# Fri3D_2020_GameOn_02.net
KiCad netlist of a schematic drawn in Altium Designer
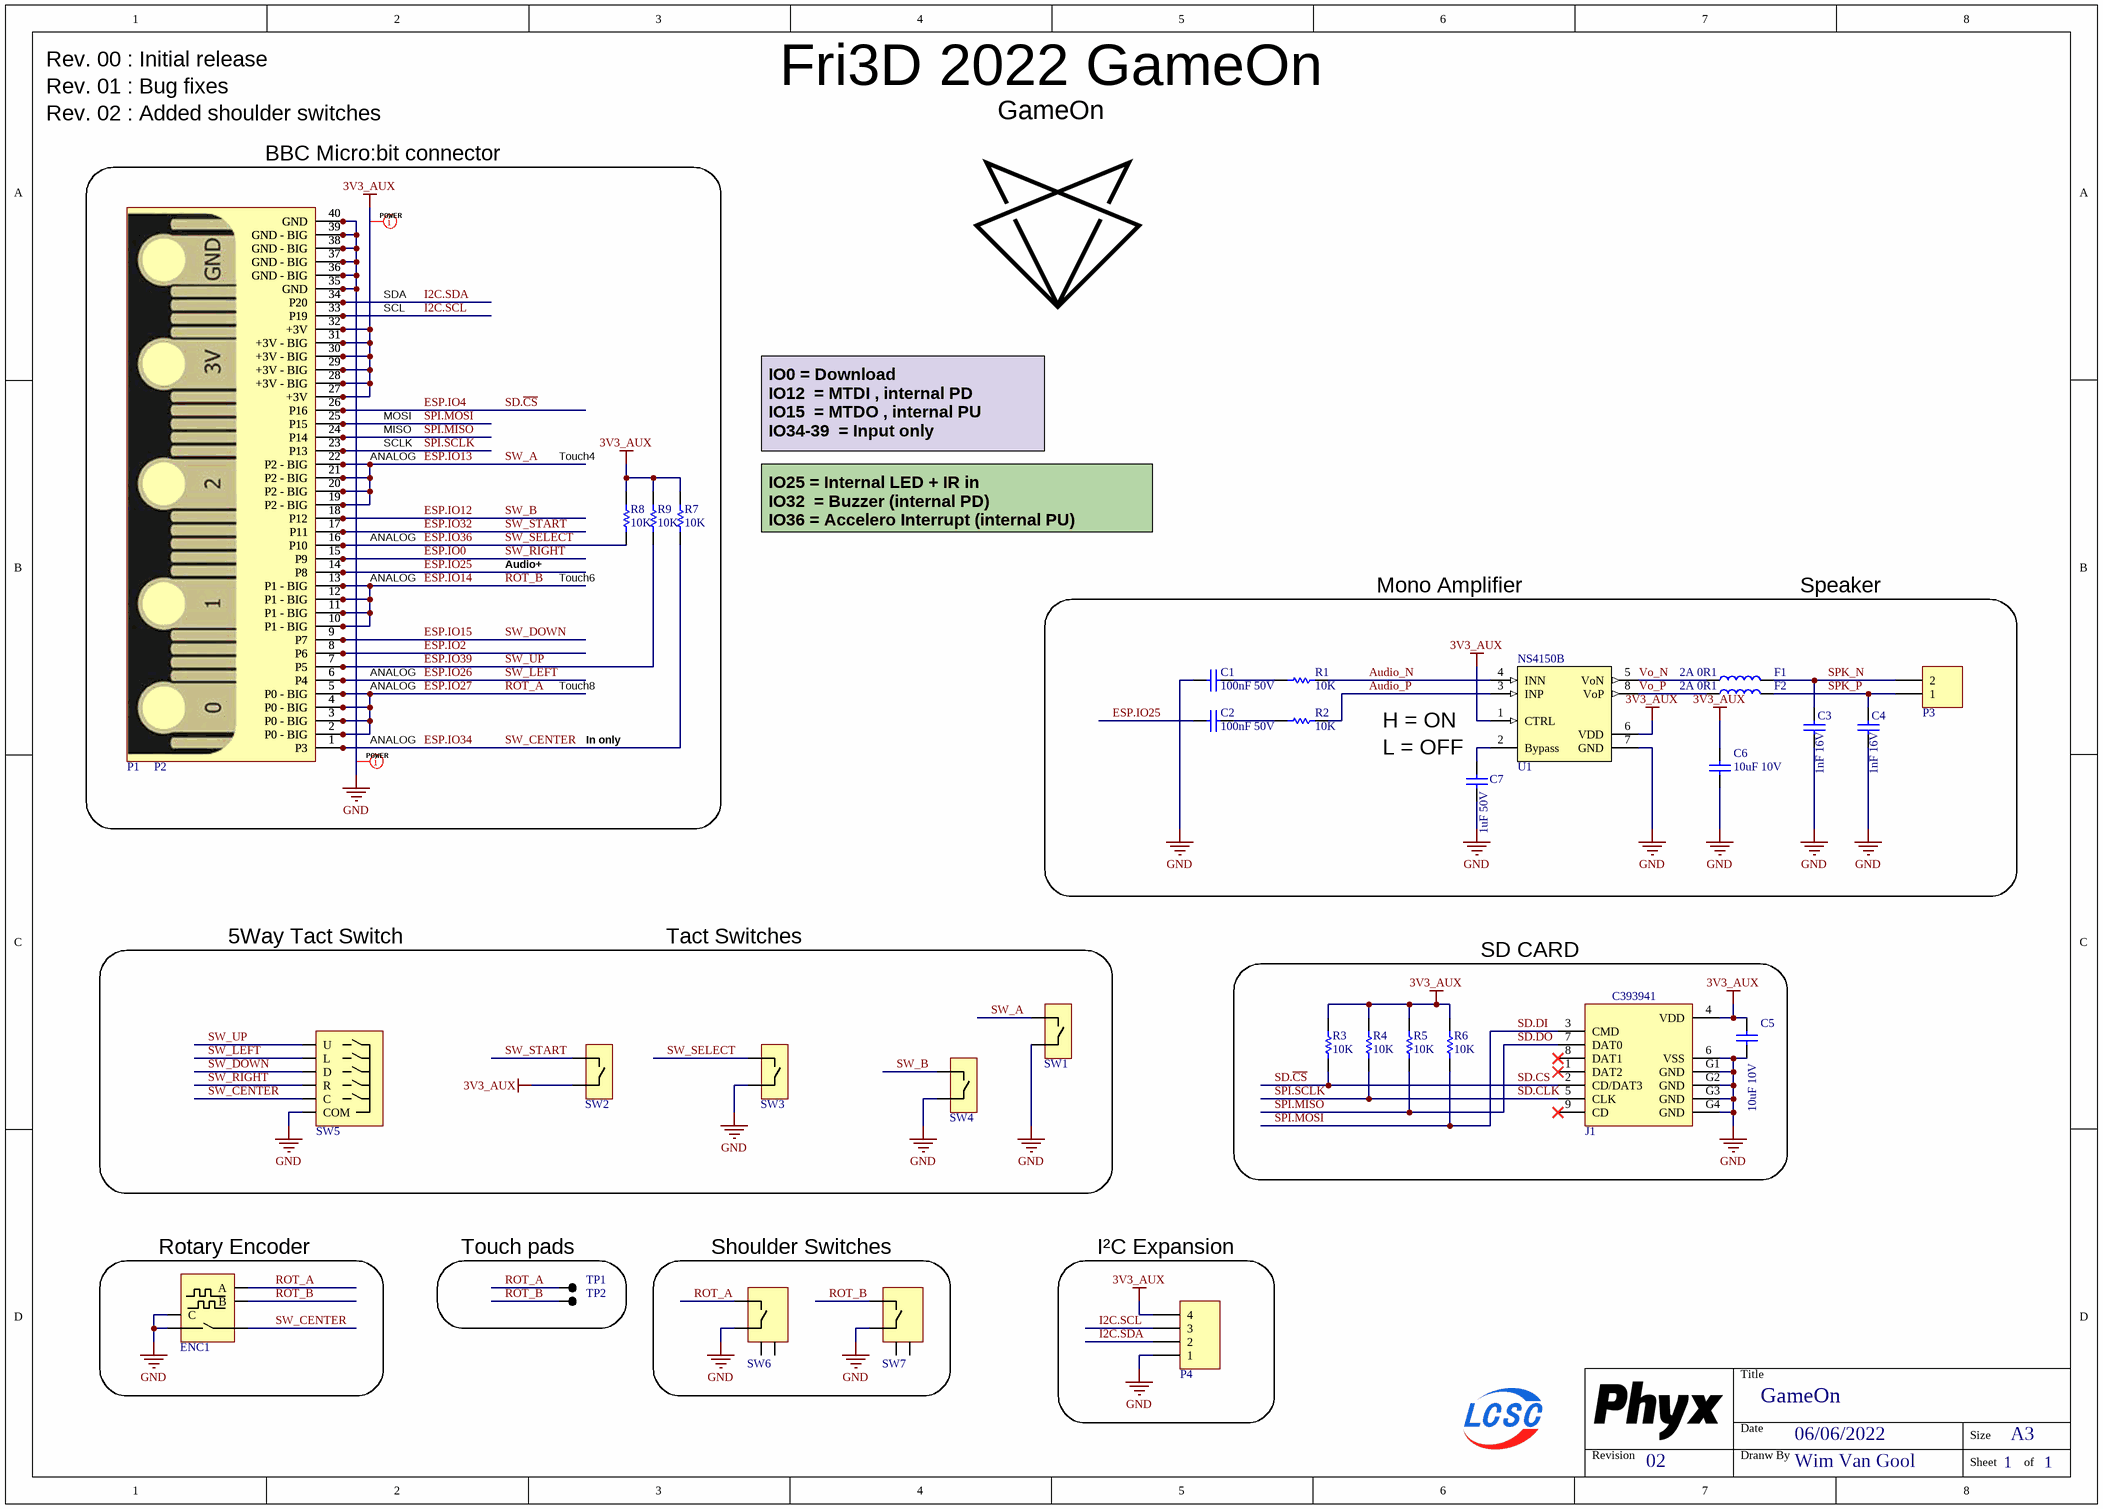
[diagram p0: Fri3D_2020_GameOn_02.SchDoc]

(export (version "E")
  (design (tool "Eeschema 10.0.6"))
  (components
    (comp (ref "C1")
      (value "100nF 50V")
      (footprint "C0603_N")
      (description "Capacitor Ceramic")
      (fields (field (name "Comment") "CAP_CERAMIC"))
      (libsource (lib "Phyx_Components") (part "CAP_CERAMIC"))
    )
    (comp (ref "C2")
      (value "100nF 50V")
      (footprint "C0603_N")
      (description "Capacitor Ceramic")
      (fields (field (name "Comment") "CAP_CERAMIC"))
      (libsource (lib "Phyx_Components") (part "CAP_CERAMIC"))
    )
    (comp (ref "C3")
      (value "1nF 16V")
      (footprint "C0603_N")
      (description "Capacitor Ceramic")
      (fields (field (name "Comment") "CAP_CERAMIC"))
      (libsource (lib "Phyx_Components") (part "CAP_CERAMIC"))
    )
    (comp (ref "C4")
      (value "1nF 16V")
      (footprint "C0603_N")
      (description "Capacitor Ceramic")
      (fields (field (name "Comment") "CAP_CERAMIC"))
      (libsource (lib "Phyx_Components") (part "CAP_CERAMIC"))
    )
    (comp (ref "C5")
      (value "10uF 10V")
      (footprint "C0805_N")
      (description "Capacitor Ceramic")
      (fields (field (name "Comment") "CAP_CERAMIC"))
      (libsource (lib "Phyx_Components") (part "CAP_CERAMIC"))
    )
    (comp (ref "C6")
      (value "10uF 10V")
      (footprint "C0805_N")
      (description "Capacitor Ceramic")
      (fields (field (name "Comment") "CAP_CERAMIC"))
      (libsource (lib "Phyx_Components") (part "CAP_CERAMIC"))
    )
    (comp (ref "C7")
      (value "1uF 50V")
      (footprint "C0603_N")
      (description "Capacitor Ceramic")
      (fields (field (name "Comment") "CAP_CERAMIC"))
      (libsource (lib "Phyx_Components") (part "CAP_CERAMIC"))
    )
    (comp (ref "ENC1")
      (value "Rotary Encoder with Switch")
      (footprint "PEC11-4215F-S0024")
      (libsource (lib "Phyx_Components") (part "ROT_ENC_3P_SW"))
    )
    (comp (ref "F1")
      (value "2A 0R1")
      (footprint "L0805")
      (fields (field (name "Comment") "FERRITE"))
      (libsource (lib "Phyx_Components") (part "FERRITE"))
    )
    (comp (ref "F2")
      (value "2A 0R1")
      (footprint "L0805")
      (fields (field (name "Comment") "FERRITE"))
      (libsource (lib "Phyx_Components") (part "FERRITE"))
    )
    (comp (ref "J1")
      (value "Micro SD PiPo Push-Push")
      (footprint "TFP09-2-12B")
      (description "=Description")
      (fields (field (name "SUPPLIER PART NUMBER 1") "C393941"))
      (libsource (lib "Phyx_Components") (part "TFP09-2-12B"))
    )
    (comp (ref "P1")
      (value "MicroBit 90deg connector Cylconn")
      (footprint "MicroBIT_CYLCONN_SMD_90")
      (libsource (lib "Phyx_Components") (part "Header 40_MicroBit"))
    )
    (comp (ref "P2")
      (value "MicroBit 180deg connector Cylconn")
      (footprint "MicroBIT_CYLCONN_SMD_180")
      (libsource (lib "Phyx_Components") (part "Header 40_MicroBit"))
    )
    (comp (ref "P3")
      (value "Header 2")
      (footprint "HDR1X2")
      (libsource (lib "Phyx_Components") (part "Header 2"))
    )
    (comp (ref "P4")
      (value "Header 4")
      (footprint "HDR1X4")
      (libsource (lib "Phyx_Components") (part "Header 4"))
    )
    (comp (ref "R1")
      (value "10K")
      (footprint "R0603_N")
      (fields (field (name "Comment") "RESISTOR"))
      (libsource (lib "Phyx_Components") (part "RESISTOR"))
    )
    (comp (ref "R2")
      (value "10K")
      (footprint "R0603_N")
      (fields (field (name "Comment") "RESISTOR"))
      (libsource (lib "Phyx_Components") (part "RESISTOR"))
    )
    (comp (ref "R3")
      (value "10K")
      (footprint "R0603_N")
      (fields (field (name "Comment") "RESISTOR"))
      (libsource (lib "Phyx_Components") (part "RESISTOR"))
    )
    (comp (ref "R4")
      (value "10K")
      (footprint "R0603_N")
      (fields (field (name "Comment") "RESISTOR"))
      (libsource (lib "Phyx_Components") (part "RESISTOR"))
    )
    (comp (ref "R5")
      (value "10K")
      (footprint "R0603_N")
      (fields (field (name "Comment") "RESISTOR"))
      (libsource (lib "Phyx_Components") (part "RESISTOR"))
    )
    (comp (ref "R6")
      (value "10K")
      (footprint "R0603_N")
      (fields (field (name "Comment") "RESISTOR"))
      (libsource (lib "Phyx_Components") (part "RESISTOR"))
    )
    (comp (ref "R7")
      (value "10K")
      (footprint "R0603_N")
      (fields (field (name "Comment") "RESISTOR"))
      (libsource (lib "Phyx_Components") (part "RESISTOR"))
    )
    (comp (ref "R8")
      (value "10K")
      (footprint "R0603_N")
      (fields (field (name "Comment") "RESISTOR"))
      (libsource (lib "Phyx_Components") (part "RESISTOR"))
    )
    (comp (ref "R9")
      (value "10K")
      (footprint "R0603_N")
      (fields (field (name "Comment") "RESISTOR"))
      (libsource (lib "Phyx_Components") (part "RESISTOR"))
    )
    (comp (ref "SW1")
      (value "Default TH TACT")
      (footprint "TACTSW")
      (libsource (lib "Phyx_Components") (part "SW_TACT"))
    )
    (comp (ref "SW2")
      (value "Default TH TACT")
      (footprint "TACTSW")
      (libsource (lib "Phyx_Components") (part "SW_TACT"))
    )
    (comp (ref "SW3")
      (value "Default TH TACT")
      (footprint "TACTSW")
      (libsource (lib "Phyx_Components") (part "SW_TACT"))
    )
    (comp (ref "SW4")
      (value "Default TH TACT")
      (footprint "TACTSW")
      (libsource (lib "Phyx_Components") (part "SW_TACT"))
    )
    (comp (ref "SW5")
      (value "5Way Tact switch")
      (footprint "TACTSW_5W_K1-1506DN-01")
      (libsource (lib "Phyx_Components") (part "SW_TACT_5WAY"))
    )
    (comp (ref "SW6")
      (value "Tact switch, RA, 3,85mm")
      (footprint "TACTSW_RA_385")
      (libsource (lib "Phyx_Components") (part "SW_TACT_RA"))
    )
    (comp (ref "SW7")
      (value "Tact switch, RA, 3,85mm")
      (footprint "TACTSW_RA_385")
      (libsource (lib "Phyx_Components") (part "SW_TACT_RA"))
    )
    (comp (ref "TP1")
      (value "TEST_PAD")
      (footprint "TP_1.2mm")
      (libsource (lib "Phyx_Components") (part "TEST_PAD"))
    )
    (comp (ref "TP2")
      (value "TEST_PAD")
      (footprint "TP_1.2mm")
      (libsource (lib "Phyx_Components") (part "TEST_PAD"))
    )
    (comp (ref "U1")
      (value "NS4150B")
      (footprint "MAX_uSOP8")
      (description "=Description")
      (fields (field (name "Comment") "5W Class D mono amplifier inducter-less Differential input MSOP8"))
      (libsource (lib "Phyx_Components") (part "NS4150"))
    )
  )
  (nets
    (net (code "1") (name "/Audio_N") (class "Default")
      (node (ref "R1") (pin "2") (pinfunction "2_2") (pintype "passive"))
      (node (ref "U1") (pin "4") (pinfunction "INN_4") (pintype "input"))
    )
    (net (code "2") (name "/Audio_P") (class "Default")
      (node (ref "R2") (pin "2") (pinfunction "2_2") (pintype "passive"))
      (node (ref "U1") (pin "3") (pinfunction "INP_3") (pintype "input"))
    )
    (net (code "3") (name "/ESP.IO0") (class "Default")
      (node (ref "P1") (pin "15") (pinfunction "P9_15") (pintype "passive"))
      (node (ref "P2") (pin "15") (pinfunction "P9_15") (pintype "passive"))
      (node (ref "SW5") (pin "5") (pinfunction "R_5") (pintype "passive"))
    )
    (net (code "4") (name "/ESP.IO2") (class "Default")
      (node (ref "P1") (pin "8") (pinfunction "P6_8") (pintype "passive"))
      (node (ref "P2") (pin "8") (pinfunction "P6_8") (pintype "passive"))
    )
    (net (code "5") (name "/ESP.IO4") (class "Default")
      (node (ref "J1") (pin "2") (pinfunction "CD/DAT3_2") (pintype "passive"))
      (node (ref "P1") (pin "26") (pinfunction "P16_26") (pintype "passive"))
      (node (ref "P2") (pin "26") (pinfunction "P16_26") (pintype "passive"))
      (node (ref "R3") (pin "2") (pinfunction "2_2") (pintype "passive"))
    )
    (net (code "6") (name "/ESP.IO12") (class "Default")
      (node (ref "P1") (pin "18") (pinfunction "P12_18") (pintype "passive"))
      (node (ref "P2") (pin "18") (pinfunction "P12_18") (pintype "passive"))
      (node (ref "SW4") (pin "1") (pinfunction "1_1") (pintype "passive"))
    )
    (net (code "7") (name "/ESP.IO13") (class "Default")
      (node (ref "P1") (pin "19") (pinfunction "P2_-_BIG_19") (pintype "passive"))
      (node (ref "P1") (pin "20") (pinfunction "P2_-_BIG_20") (pintype "passive"))
      (node (ref "P1") (pin "21") (pinfunction "P2_-_BIG_21") (pintype "passive"))
      (node (ref "P1") (pin "22") (pinfunction "P2_-_BIG_22") (pintype "passive"))
      (node (ref "P2") (pin "19") (pinfunction "P2_-_BIG_19") (pintype "passive"))
      (node (ref "P2") (pin "20") (pinfunction "P2_-_BIG_20") (pintype "passive"))
      (node (ref "P2") (pin "21") (pinfunction "P2_-_BIG_21") (pintype "passive"))
      (node (ref "P2") (pin "22") (pinfunction "P2_-_BIG_22") (pintype "passive"))
      (node (ref "SW1") (pin "1") (pinfunction "1_1") (pintype "passive"))
    )
    (net (code "8") (name "/ESP.IO14") (class "Default")
      (node (ref "ENC1") (pin "B") (pinfunction "B_B") (pintype "passive"))
      (node (ref "P1") (pin "10") (pinfunction "P1_-_BIG_10") (pintype "passive"))
      (node (ref "P1") (pin "11") (pinfunction "P1_-_BIG_11") (pintype "passive"))
      (node (ref "P1") (pin "12") (pinfunction "P1_-_BIG_12") (pintype "passive"))
      (node (ref "P1") (pin "13") (pinfunction "P1_-_BIG_13") (pintype "passive"))
      (node (ref "P2") (pin "10") (pinfunction "P1_-_BIG_10") (pintype "passive"))
      (node (ref "P2") (pin "11") (pinfunction "P1_-_BIG_11") (pintype "passive"))
      (node (ref "P2") (pin "12") (pinfunction "P1_-_BIG_12") (pintype "passive"))
      (node (ref "P2") (pin "13") (pinfunction "P1_-_BIG_13") (pintype "passive"))
      (node (ref "SW7") (pin "1") (pinfunction "1_1") (pintype "passive"))
      (node (ref "TP2") (pin "1") (pinfunction "1_1") (pintype "passive"))
    )
    (net (code "9") (name "/ESP.IO15") (class "Default")
      (node (ref "P1") (pin "9") (pinfunction "P7_9") (pintype "passive"))
      (node (ref "P2") (pin "9") (pinfunction "P7_9") (pintype "passive"))
      (node (ref "SW5") (pin "3") (pinfunction "D_3") (pintype "passive"))
    )
    (net (code "10") (name "/ESP.IO25") (class "Default")
      (node (ref "C2") (pin "2") (pinfunction "2_2") (pintype "passive"))
      (node (ref "P1") (pin "14") (pinfunction "P8_14") (pintype "passive"))
      (node (ref "P2") (pin "14") (pinfunction "P8_14") (pintype "passive"))
    )
    (net (code "11") (name "/ESP.IO26") (class "Default")
      (node (ref "P1") (pin "6") (pinfunction "P4_6") (pintype "passive"))
      (node (ref "P2") (pin "6") (pinfunction "P4_6") (pintype "passive"))
      (node (ref "SW5") (pin "2") (pinfunction "L_2") (pintype "passive"))
    )
    (net (code "12") (name "/ESP.IO27") (class "Default")
      (node (ref "ENC1") (pin "A") (pinfunction "A_A") (pintype "passive"))
      (node (ref "P1") (pin "2") (pinfunction "P0_-_BIG_2") (pintype "passive"))
      (node (ref "P1") (pin "3") (pinfunction "P0_-_BIG_3") (pintype "passive"))
      (node (ref "P1") (pin "4") (pinfunction "P0_-_BIG_4") (pintype "passive"))
      (node (ref "P1") (pin "5") (pinfunction "P0_-_BIG_5") (pintype "passive"))
      (node (ref "P2") (pin "2") (pinfunction "P0_-_BIG_2") (pintype "passive"))
      (node (ref "P2") (pin "3") (pinfunction "P0_-_BIG_3") (pintype "passive"))
      (node (ref "P2") (pin "4") (pinfunction "P0_-_BIG_4") (pintype "passive"))
      (node (ref "P2") (pin "5") (pinfunction "P0_-_BIG_5") (pintype "passive"))
      (node (ref "SW6") (pin "1") (pinfunction "1_1") (pintype "passive"))
      (node (ref "TP1") (pin "1") (pinfunction "1_1") (pintype "passive"))
    )
    (net (code "13") (name "/ESP.IO32") (class "Default")
      (node (ref "P1") (pin "17") (pinfunction "P11_17") (pintype "passive"))
      (node (ref "P2") (pin "17") (pinfunction "P11_17") (pintype "passive"))
      (node (ref "SW2") (pin "1") (pinfunction "1_1") (pintype "passive"))
    )
    (net (code "14") (name "/ESP.IO34") (class "Default")
      (node (ref "ENC1") (pin "2") (pinfunction "2_2") (pintype "passive"))
      (node (ref "P1") (pin "1") (pinfunction "P3_1") (pintype "passive"))
      (node (ref "P2") (pin "1") (pinfunction "P3_1") (pintype "passive"))
      (node (ref "R7") (pin "2") (pinfunction "2_2") (pintype "passive"))
      (node (ref "SW5") (pin "6") (pinfunction "C_6") (pintype "passive"))
    )
    (net (code "15") (name "/ESP.IO36") (class "Default")
      (node (ref "P1") (pin "16") (pinfunction "P10_16") (pintype "passive"))
      (node (ref "P2") (pin "16") (pinfunction "P10_16") (pintype "passive"))
      (node (ref "R8") (pin "2") (pinfunction "2_2") (pintype "passive"))
      (node (ref "SW3") (pin "1") (pinfunction "1_1") (pintype "passive"))
    )
    (net (code "16") (name "/ESP.IO39") (class "Default")
      (node (ref "P1") (pin "7") (pinfunction "P5_7") (pintype "passive"))
      (node (ref "P2") (pin "7") (pinfunction "P5_7") (pintype "passive"))
      (node (ref "R9") (pin "2") (pinfunction "2_2") (pintype "passive"))
      (node (ref "SW5") (pin "1") (pinfunction "U_1") (pintype "passive"))
    )
    (net (code "17") (name "/I2C.SCL") (class "Default")
      (node (ref "P1") (pin "33") (pinfunction "P19_33") (pintype "passive"))
      (node (ref "P2") (pin "33") (pinfunction "P19_33") (pintype "passive"))
      (node (ref "P4") (pin "3") (pinfunction "3_3") (pintype "passive"))
    )
    (net (code "18") (name "/I2C.SDA") (class "Default")
      (node (ref "P1") (pin "34") (pinfunction "P20_34") (pintype "passive"))
      (node (ref "P2") (pin "34") (pinfunction "P20_34") (pintype "passive"))
      (node (ref "P4") (pin "2") (pinfunction "2_2") (pintype "passive"))
    )
    (net (code "19") (name "/SD.CLK") (class "Default")
      (node (ref "J1") (pin "5") (pinfunction "CLK_5") (pintype "passive"))
      (node (ref "P1") (pin "23") (pinfunction "P13_23") (pintype "passive"))
      (node (ref "P2") (pin "23") (pinfunction "P13_23") (pintype "passive"))
      (node (ref "R4") (pin "2") (pinfunction "2_2") (pintype "passive"))
    )
    (net (code "20") (name "/SD.DI") (class "Default")
      (node (ref "J1") (pin "3") (pinfunction "CMD_3") (pintype "passive"))
      (node (ref "P1") (pin "25") (pinfunction "P15_25") (pintype "passive"))
      (node (ref "P2") (pin "25") (pinfunction "P15_25") (pintype "passive"))
      (node (ref "R6") (pin "2") (pinfunction "2_2") (pintype "passive"))
    )
    (net (code "21") (name "/SD.DO") (class "Default")
      (node (ref "J1") (pin "7") (pinfunction "DAT0_7") (pintype "passive"))
      (node (ref "P1") (pin "24") (pinfunction "P14_24") (pintype "passive"))
      (node (ref "P2") (pin "24") (pinfunction "P14_24") (pintype "passive"))
      (node (ref "R5") (pin "2") (pinfunction "2_2") (pintype "passive"))
    )
    (net (code "22") (name "/SPK_N") (class "Default")
      (node (ref "C3") (pin "1") (pinfunction "1_1") (pintype "passive"))
      (node (ref "F1") (pin "2") (pinfunction "2_2") (pintype "passive"))
      (node (ref "P3") (pin "2") (pinfunction "2_2") (pintype "passive"))
    )
    (net (code "23") (name "/SPK_P") (class "Default")
      (node (ref "C4") (pin "1") (pinfunction "1_1") (pintype "passive"))
      (node (ref "F2") (pin "2") (pinfunction "2_2") (pintype "passive"))
      (node (ref "P3") (pin "1") (pinfunction "1_1") (pintype "passive"))
    )
    (net (code "24") (name "/Vo_N") (class "Default")
      (node (ref "F1") (pin "1") (pinfunction "1_1") (pintype "passive"))
      (node (ref "U1") (pin "5") (pinfunction "VoN_5") (pintype "output"))
    )
    (net (code "25") (name "/Vo_P") (class "Default")
      (node (ref "F2") (pin "1") (pinfunction "1_1") (pintype "passive"))
      (node (ref "U1") (pin "8") (pinfunction "VoP_8") (pintype "output"))
    )
    (net (code "26") (name "3V3_AUX") (class "Default")
      (node (ref "C5") (pin "1") (pinfunction "1_1") (pintype "passive"))
      (node (ref "C6") (pin "1") (pinfunction "1_1") (pintype "passive"))
      (node (ref "J1") (pin "4") (pinfunction "VDD_4") (pintype "power_in"))
      (node (ref "P1") (pin "27") (pinfunction "+3V_27") (pintype "passive"))
      (node (ref "P1") (pin "28") (pinfunction "+3V_-_BIG_28") (pintype "passive"))
      (node (ref "P1") (pin "29") (pinfunction "+3V_-_BIG_29") (pintype "passive"))
      (node (ref "P1") (pin "30") (pinfunction "+3V_-_BIG_30") (pintype "passive"))
      (node (ref "P1") (pin "31") (pinfunction "+3V_-_BIG_31") (pintype "passive"))
      (node (ref "P1") (pin "32") (pinfunction "+3V_32") (pintype "passive"))
      (node (ref "P2") (pin "27") (pinfunction "+3V_27") (pintype "passive"))
      (node (ref "P2") (pin "28") (pinfunction "+3V_-_BIG_28") (pintype "passive"))
      (node (ref "P2") (pin "29") (pinfunction "+3V_-_BIG_29") (pintype "passive"))
      (node (ref "P2") (pin "30") (pinfunction "+3V_-_BIG_30") (pintype "passive"))
      (node (ref "P2") (pin "31") (pinfunction "+3V_-_BIG_31") (pintype "passive"))
      (node (ref "P2") (pin "32") (pinfunction "+3V_32") (pintype "passive"))
      (node (ref "P4") (pin "4") (pinfunction "4_4") (pintype "passive"))
      (node (ref "R3") (pin "1") (pinfunction "1_1") (pintype "passive"))
      (node (ref "R4") (pin "1") (pinfunction "1_1") (pintype "passive"))
      (node (ref "R5") (pin "1") (pinfunction "1_1") (pintype "passive"))
      (node (ref "R6") (pin "1") (pinfunction "1_1") (pintype "passive"))
      (node (ref "R7") (pin "1") (pinfunction "1_1") (pintype "passive"))
      (node (ref "R8") (pin "1") (pinfunction "1_1") (pintype "passive"))
      (node (ref "R9") (pin "1") (pinfunction "1_1") (pintype "passive"))
      (node (ref "SW2") (pin "2") (pinfunction "2_2") (pintype "passive"))
      (node (ref "U1") (pin "1") (pinfunction "CTRL_1") (pintype "input"))
      (node (ref "U1") (pin "6") (pinfunction "VDD_6") (pintype "power_in"))
    )
    (net (code "27") (name "GND") (class "Default")
      (node (ref "C1") (pin "2") (pinfunction "2_2") (pintype "passive"))
      (node (ref "C3") (pin "2") (pinfunction "2_2") (pintype "passive"))
      (node (ref "C4") (pin "2") (pinfunction "2_2") (pintype "passive"))
      (node (ref "C5") (pin "2") (pinfunction "2_2") (pintype "passive"))
      (node (ref "C6") (pin "2") (pinfunction "2_2") (pintype "passive"))
      (node (ref "C7") (pin "2") (pinfunction "2_2") (pintype "passive"))
      (node (ref "ENC1") (pin "1") (pinfunction "1_1") (pintype "passive"))
      (node (ref "ENC1") (pin "C") (pinfunction "C_C") (pintype "passive"))
      (node (ref "J1") (pin "6") (pinfunction "VSS_6") (pintype "power_in"))
      (node (ref "J1") (pin "G1") (pinfunction "GND_G1") (pintype "power_in"))
      (node (ref "J1") (pin "G2") (pinfunction "GND_G2") (pintype "power_in"))
      (node (ref "J1") (pin "G3") (pinfunction "GND_G3") (pintype "power_in"))
      (node (ref "J1") (pin "G4") (pinfunction "GND_G4") (pintype "power_in"))
      (node (ref "P1") (pin "35") (pinfunction "GND_35") (pintype "passive"))
      (node (ref "P1") (pin "36") (pinfunction "GND_-_BIG_36") (pintype "passive"))
      (node (ref "P1") (pin "37") (pinfunction "GND_-_BIG_37") (pintype "passive"))
      (node (ref "P1") (pin "38") (pinfunction "GND_-_BIG_38") (pintype "passive"))
      (node (ref "P1") (pin "39") (pinfunction "GND_-_BIG_39") (pintype "passive"))
      (node (ref "P1") (pin "40") (pinfunction "GND_40") (pintype "passive"))
      (node (ref "P2") (pin "35") (pinfunction "GND_35") (pintype "passive"))
      (node (ref "P2") (pin "36") (pinfunction "GND_-_BIG_36") (pintype "passive"))
      (node (ref "P2") (pin "37") (pinfunction "GND_-_BIG_37") (pintype "passive"))
      (node (ref "P2") (pin "38") (pinfunction "GND_-_BIG_38") (pintype "passive"))
      (node (ref "P2") (pin "39") (pinfunction "GND_-_BIG_39") (pintype "passive"))
      (node (ref "P2") (pin "40") (pinfunction "GND_40") (pintype "passive"))
      (node (ref "P4") (pin "1") (pinfunction "1_1") (pintype "passive"))
      (node (ref "SW1") (pin "2") (pinfunction "2_2") (pintype "passive"))
      (node (ref "SW3") (pin "2") (pinfunction "2_2") (pintype "passive"))
      (node (ref "SW4") (pin "2") (pinfunction "2_2") (pintype "passive"))
      (node (ref "SW5") (pin "4") (pinfunction "COM_4") (pintype "passive"))
      (node (ref "SW6") (pin "2") (pinfunction "2_2") (pintype "passive"))
      (node (ref "SW7") (pin "2") (pinfunction "2_2") (pintype "passive"))
      (node (ref "U1") (pin "7") (pinfunction "GND_7") (pintype "power_in"))
    )
    (net (code "28") (name "Net-(C1-Pad1)") (class "Default")
      (node (ref "C1") (pin "1") (pinfunction "1_1") (pintype "passive"))
      (node (ref "R1") (pin "1") (pinfunction "1_1") (pintype "passive"))
    )
    (net (code "29") (name "Net-(C2-Pad1)") (class "Default")
      (node (ref "C2") (pin "1") (pinfunction "1_1") (pintype "passive"))
      (node (ref "R2") (pin "1") (pinfunction "1_1") (pintype "passive"))
    )
    (net (code "30") (name "Net-(U1-Bypass)") (class "Default")
      (node (ref "C7") (pin "1") (pinfunction "1_1") (pintype "passive"))
      (node (ref "U1") (pin "2") (pinfunction "Bypass_2") (pintype "passive"))
    )
    (net (code "31") (name "unconnected-(J1-CD-Pad9)") (class "Default")
      (node (ref "J1") (pin "9") (pinfunction "CD_9") (pintype "passive+no_connect"))
    )
    (net (code "32") (name "unconnected-(J1-DAT1-Pad8)") (class "Default")
      (node (ref "J1") (pin "8") (pinfunction "DAT1_8") (pintype "passive+no_connect"))
    )
    (net (code "33") (name "unconnected-(J1-DAT2-Pad1)") (class "Default")
      (node (ref "J1") (pin "1") (pinfunction "DAT2_1") (pintype "passive+no_connect"))
    )
    (net (code "34") (name "unconnected-(SW6-PadMH1)") (class "Default")
      (node (ref "SW6") (pin "MH1") (pinfunction "MH1_MH1") (pintype "passive"))
    )
    (net (code "35") (name "unconnected-(SW6-PadMH2)") (class "Default")
      (node (ref "SW6") (pin "MH2") (pinfunction "MH2_MH2") (pintype "passive"))
    )
    (net (code "36") (name "unconnected-(SW7-PadMH1)") (class "Default")
      (node (ref "SW7") (pin "MH1") (pinfunction "MH1_MH1") (pintype "passive"))
    )
    (net (code "37") (name "unconnected-(SW7-PadMH2)") (class "Default")
      (node (ref "SW7") (pin "MH2") (pinfunction "MH2_MH2") (pintype "passive"))
    )
  )
)
